# M5_STACK_STAMP_C3_ISOBUS_JSTex.net
KiCad netlist of a schematic drawn in EAGLE
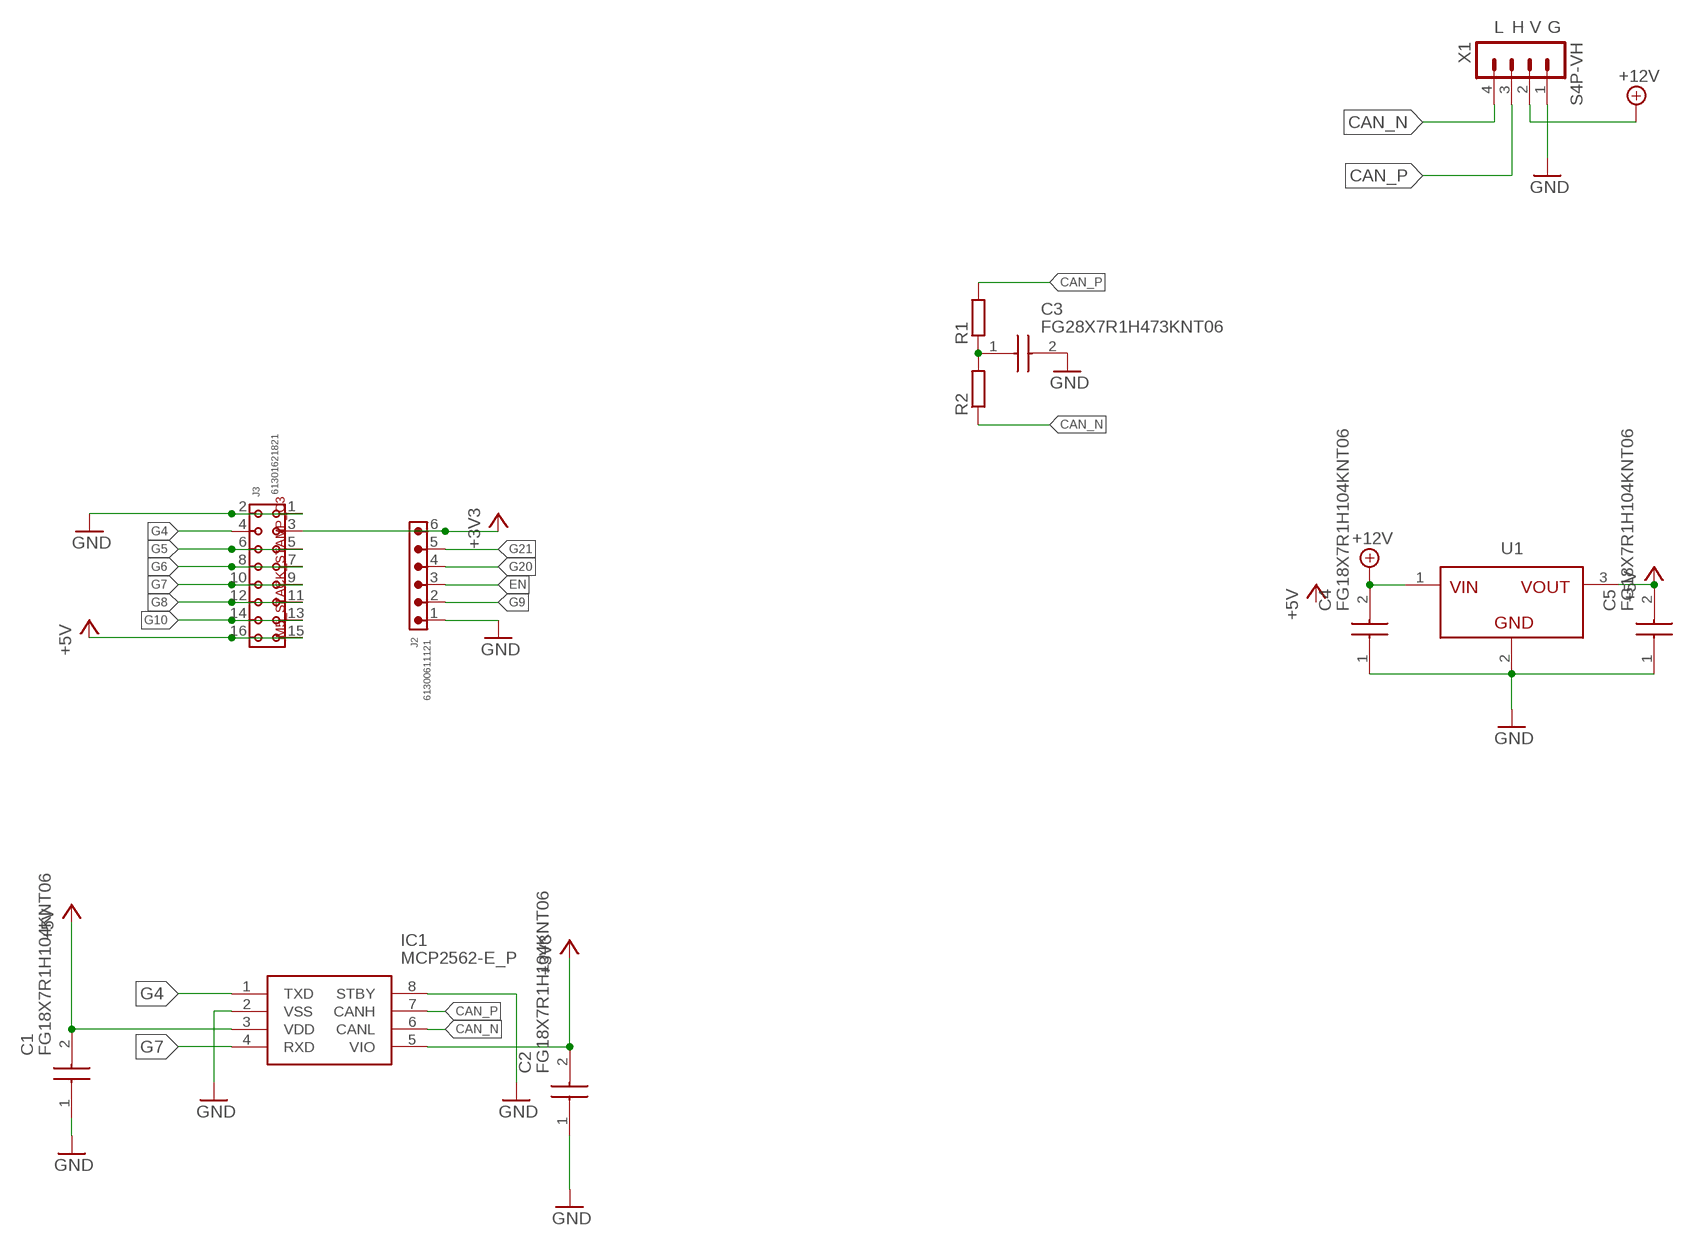
[diagram p0: schematic, sheet 1]

(export (version "E")
  (design (tool "Eeschema 10.0.6"))
  (components
    (comp (ref "C1")
      (value "FG18X7R1H104KNT06")
      (footprint "eagle-import:FG18C0G1H101JNT06")
      (fields (field (name "MOUSER_PART_NUMBER") "810-FG18X7R1H104KNT6"))
      (libsource (lib "eagle-import") (part "FG18X7R1H104KNT06"))
    )
    (comp (ref "C2")
      (value "FG18X7R1H104KNT06")
      (footprint "eagle-import:FG18C0G1H101JNT06")
      (fields (field (name "MOUSER_PART_NUMBER") "810-FG18X7R1H104KNT6"))
      (libsource (lib "eagle-import") (part "FG18X7R1H104KNT06"))
    )
    (comp (ref "C3")
      (value "FG28X7R1H473KNT06")
      (footprint "eagle-import:FG28")
      (fields (field (name "MOUSER_PART_NUMBER") "810-FG28X7R1H473KNT6"))
      (libsource (lib "eagle-import") (part "FG28X7R1H473KNT06"))
    )
    (comp (ref "C4")
      (value "FG18X7R1H104KNT06")
      (footprint "eagle-import:FG18C0G1H101JNT06")
      (fields (field (name "MOUSER_PART_NUMBER") "810-FG18X7R1H104KNT6"))
      (libsource (lib "eagle-import") (part "FG18X7R1H104KNT06"))
    )
    (comp (ref "C5")
      (value "FG18X7R1H104KNT06")
      (footprint "eagle-import:FG18C0G1H101JNT06")
      (fields (field (name "MOUSER_PART_NUMBER") "810-FG18X7R1H104KNT6"))
      (libsource (lib "eagle-import") (part "FG18X7R1H104KNT06"))
    )
    (comp (ref "IC1")
      (value "MCP2562-E_P")
      (footprint "eagle-import:DIP781W56P254L950H533Q8N")
      (fields
        (field (name "MANUFACTURER_PART_NUMBER") "MCP2562-E/P")
        (field (name "MOUSER_PART_NUMBER") "579-MCP2562-E/P")
      )
      (libsource (lib "eagle-import") (part "MCP2562-E_P"))
    )
    (comp (ref "J2")
      (value "61300611121")
      (footprint "eagle-import:61300611121")
      (libsource (lib "eagle-import") (part "6130XX11121_61300611121"))
    )
    (comp (ref "J3")
      (value "61301621821")
      (footprint "eagle-import:61301621821")
      (libsource (lib "eagle-import") (part "6130XX21821_61301621821"))
    )
    (comp (ref "R1")
      (value "R-EU_0204/7")
      (footprint "eagle-import:0204_7")
      (libsource (lib "eagle-import") (part "R-EU_0204/7"))
    )
    (comp (ref "R2")
      (value "R-EU_0204/7")
      (footprint "eagle-import:0204_7")
      (libsource (lib "eagle-import") (part "R-EU_0204/7"))
    )
    (comp (ref "U$1")
      (value "M5_STACK_STAMP_C3")
      (footprint "eagle-import:M5_STACK_STAMP_C3")
      (libsource (lib "eagle-import") (part "M5_STACK_STAMP_C3"))
    )
    (comp (ref "U1")
      (value "MAGI³C-FDSM_SIP-3_173010542_173XXXX42")
      (footprint "eagle-import:MAGI³C-FDSM_173XXXX42")
      (libsource (lib "eagle-import") (part "MAGI³C-FDSM_SIP-3_173XXXX42_173010542"))
    )
    (comp (ref "X1")
      (value "S4P-VH")
      (footprint "eagle-import:S4P-VH")
      (libsource (lib "eagle-import") (part "S4P-VH"))
    )
  )
  (nets
    (net (code "1") (name "+3V3") (class "Default")
      (node (ref "C2") (pin "2") (pinfunction "2_2") (pintype "bidirectional"))
      (node (ref "IC1") (pin "5") (pinfunction "VIO_5") (pintype "bidirectional"))
      (node (ref "J2") (pin "6") (pinfunction "6_6") (pintype "passive"))
      (node (ref "J3") (pin "3") (pinfunction "3_3") (pintype "passive"))
    )
    (net (code "2") (name "+5V") (class "Default")
      (node (ref "C1") (pin "2") (pinfunction "2_2") (pintype "bidirectional"))
      (node (ref "C5") (pin "2") (pinfunction "2_2") (pintype "bidirectional"))
      (node (ref "IC1") (pin "3") (pinfunction "VDD_3") (pintype "bidirectional"))
      (node (ref "J3") (pin "15") (pinfunction "15_15") (pintype "passive"))
      (node (ref "J3") (pin "16") (pinfunction "16_16") (pintype "passive"))
      (node (ref "U1") (pin "3") (pinfunction "VOUT_3") (pintype "output"))
    )
    (net (code "3") (name "+12V") (class "Default")
      (node (ref "C4") (pin "2") (pinfunction "2_2") (pintype "bidirectional"))
      (node (ref "U1") (pin "1") (pinfunction "VIN_1") (pintype "input"))
      (node (ref "X1") (pin "2") (pinfunction "2_2") (pintype "passive"))
    )
    (net (code "4") (name "CAN_N") (class "Default")
      (node (ref "IC1") (pin "6") (pinfunction "CANL_6") (pintype "bidirectional"))
      (node (ref "R2") (pin "1") (pinfunction "1_1") (pintype "passive"))
      (node (ref "X1") (pin "4") (pinfunction "4_4") (pintype "passive"))
    )
    (net (code "5") (name "CAN_P") (class "Default")
      (node (ref "IC1") (pin "7") (pinfunction "CANH_7") (pintype "bidirectional"))
      (node (ref "R1") (pin "2") (pinfunction "2_2") (pintype "passive"))
      (node (ref "X1") (pin "3") (pinfunction "3_3") (pintype "passive"))
    )
    (net (code "6") (name "EN") (class "Default")
      (node (ref "J2") (pin "3") (pinfunction "3_3") (pintype "passive"))
    )
    (net (code "7") (name "G4") (class "Default")
      (node (ref "IC1") (pin "1") (pinfunction "TXD_1") (pintype "bidirectional"))
      (node (ref "J3") (pin "4") (pinfunction "4_4") (pintype "passive"))
    )
    (net (code "8") (name "G5") (class "Default")
      (node (ref "J3") (pin "5") (pinfunction "5_5") (pintype "passive"))
      (node (ref "J3") (pin "6") (pinfunction "6_6") (pintype "passive"))
    )
    (net (code "9") (name "G6") (class "Default")
      (node (ref "J3") (pin "7") (pinfunction "7_7") (pintype "passive"))
      (node (ref "J3") (pin "8") (pinfunction "8_8") (pintype "passive"))
    )
    (net (code "10") (name "G7") (class "Default")
      (node (ref "IC1") (pin "4") (pinfunction "RXD_4") (pintype "bidirectional"))
      (node (ref "J3") (pin "10") (pinfunction "10_10") (pintype "passive"))
      (node (ref "J3") (pin "9") (pinfunction "9_9") (pintype "passive"))
    )
    (net (code "11") (name "G8") (class "Default")
      (node (ref "J3") (pin "11") (pinfunction "11_11") (pintype "passive"))
      (node (ref "J3") (pin "12") (pinfunction "12_12") (pintype "passive"))
    )
    (net (code "12") (name "G9") (class "Default")
      (node (ref "J2") (pin "2") (pinfunction "2_2") (pintype "passive"))
    )
    (net (code "13") (name "G10") (class "Default")
      (node (ref "J3") (pin "13") (pinfunction "13_13") (pintype "passive"))
      (node (ref "J3") (pin "14") (pinfunction "14_14") (pintype "passive"))
    )
    (net (code "14") (name "G20") (class "Default")
      (node (ref "J2") (pin "4") (pinfunction "4_4") (pintype "passive"))
    )
    (net (code "15") (name "G21") (class "Default")
      (node (ref "J2") (pin "5") (pinfunction "5_5") (pintype "passive"))
    )
    (net (code "16") (name "GND") (class "Default")
      (node (ref "C1") (pin "1") (pinfunction "1_1") (pintype "bidirectional"))
      (node (ref "C2") (pin "1") (pinfunction "1_1") (pintype "bidirectional"))
      (node (ref "C3") (pin "2") (pinfunction "2_2") (pintype "bidirectional"))
      (node (ref "C4") (pin "1") (pinfunction "1_1") (pintype "bidirectional"))
      (node (ref "C5") (pin "1") (pinfunction "1_1") (pintype "bidirectional"))
      (node (ref "IC1") (pin "2") (pinfunction "VSS_2") (pintype "bidirectional"))
      (node (ref "IC1") (pin "8") (pinfunction "STBY_8") (pintype "bidirectional"))
      (node (ref "J2") (pin "1") (pinfunction "1_1") (pintype "passive"))
      (node (ref "J3") (pin "1") (pinfunction "1_1") (pintype "passive"))
      (node (ref "J3") (pin "2") (pinfunction "2_2") (pintype "passive"))
      (node (ref "U1") (pin "2") (pinfunction "GND_2") (pintype "passive"))
      (node (ref "X1") (pin "1") (pinfunction "1_1") (pintype "passive"))
    )
    (net (code "17") (name "Net-(C3-Pad1)") (class "Default")
      (node (ref "C3") (pin "1") (pinfunction "1_1") (pintype "bidirectional"))
      (node (ref "R1") (pin "1") (pinfunction "1_1") (pintype "passive"))
      (node (ref "R2") (pin "2") (pinfunction "2_2") (pintype "passive"))
    )
  )
)
